# CANnibal.net
KiCad netlist of a schematic drawn in EAGLE
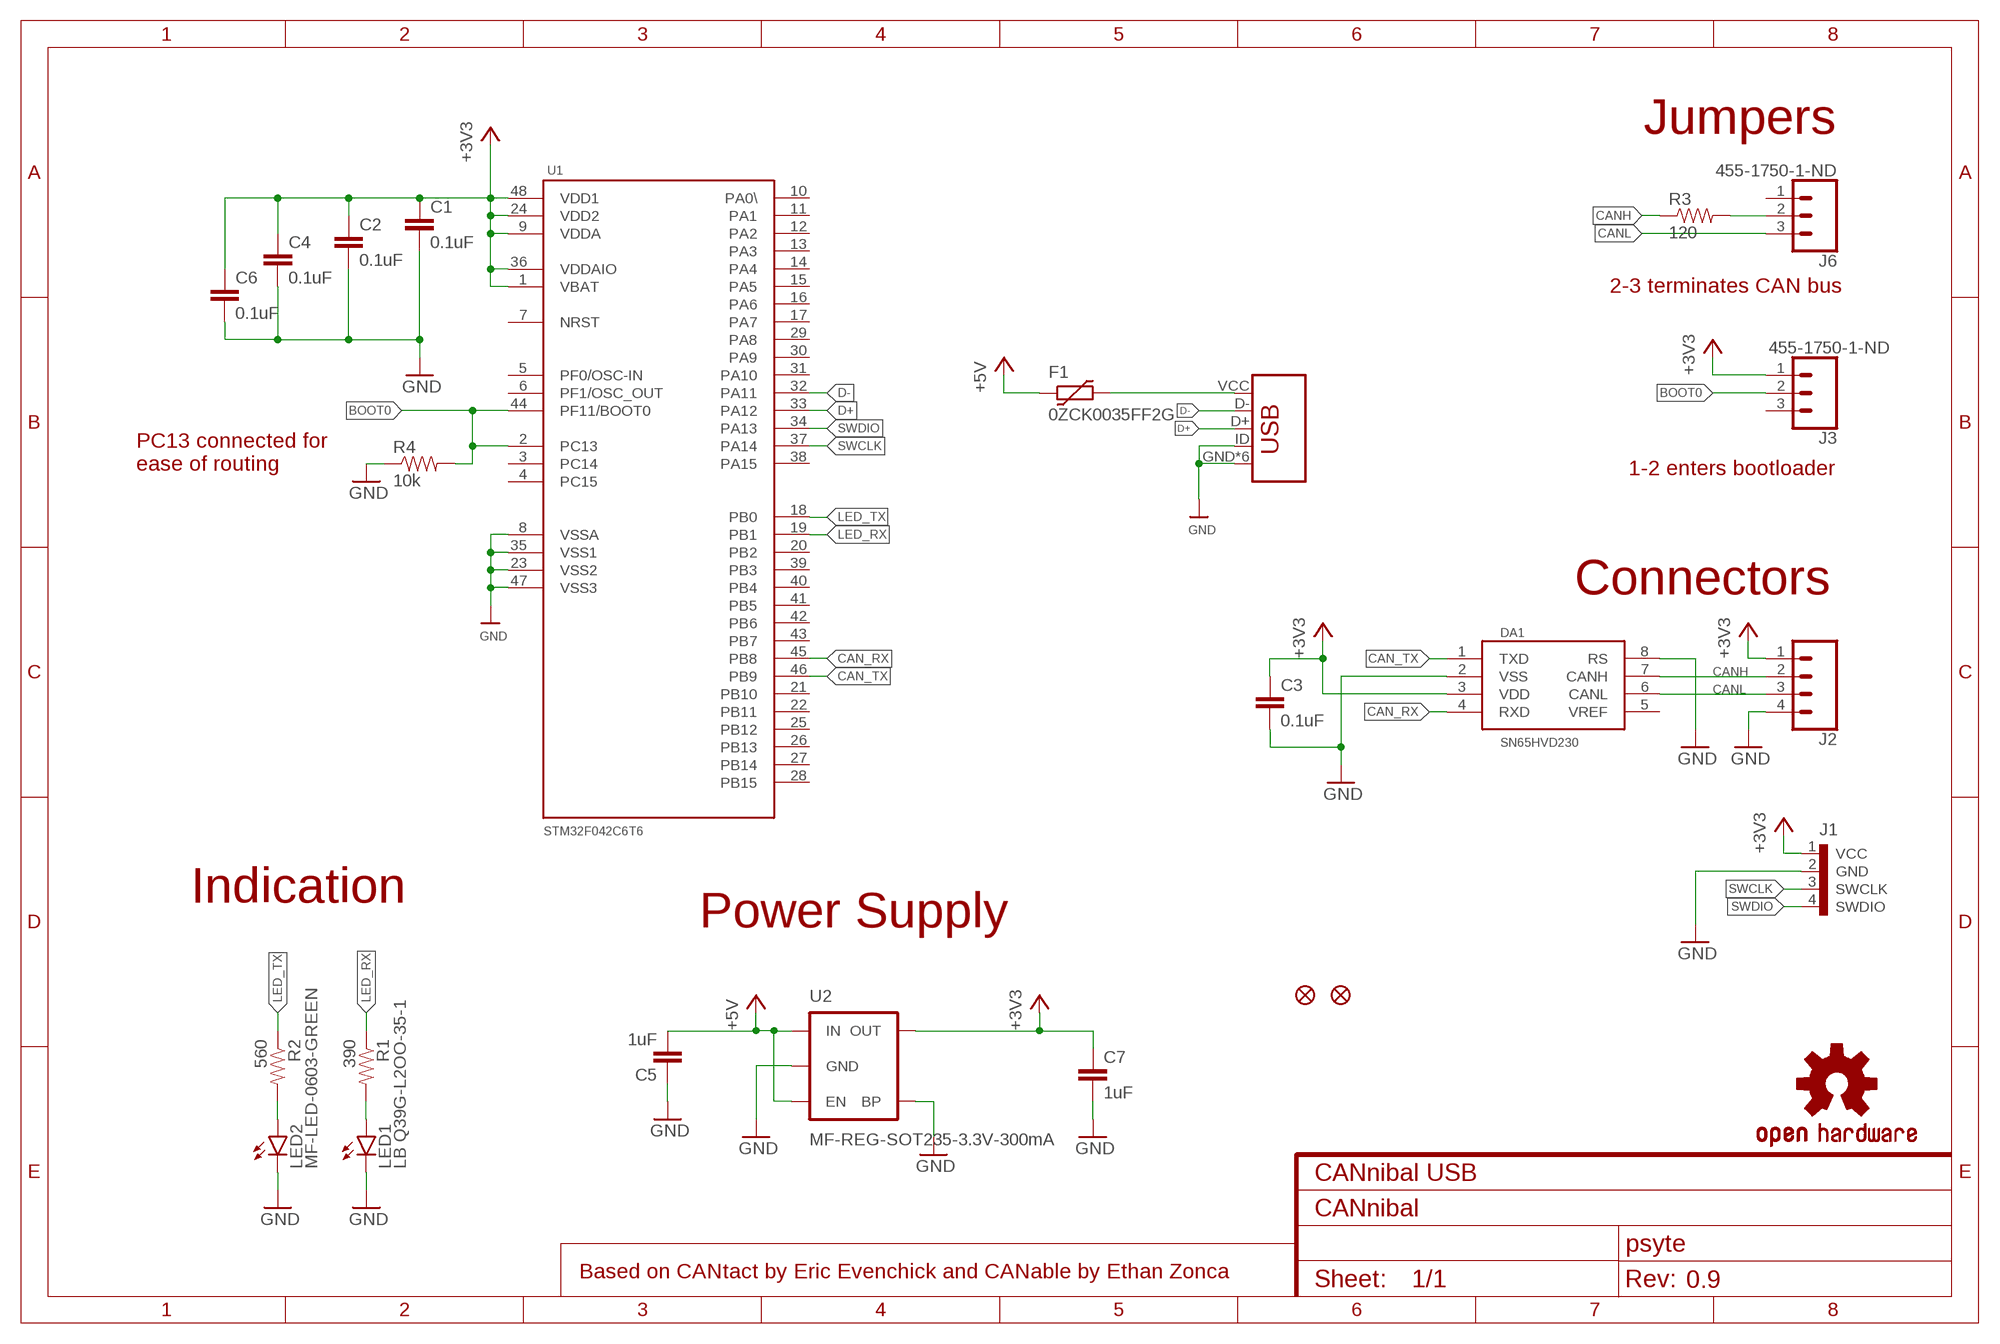
[diagram p0: schematic, sheet 1]

(export (version "E")
  (design (tool "Eeschema 10.0.6"))
  (components
    (comp (ref "C1")
      (value "0.1uF")
      (footprint "eagle-import:0603-CAP")
      (libsource (lib "eagle-import") (part "CAP0603-CAP"))
    )
    (comp (ref "C2")
      (value "0.1uF")
      (footprint "eagle-import:0603-CAP")
      (libsource (lib "eagle-import") (part "CAP0603-CAP"))
    )
    (comp (ref "C3")
      (value "0.1uF")
      (footprint "eagle-import:0603-CAP")
      (libsource (lib "eagle-import") (part "CAP0603-CAP"))
    )
    (comp (ref "C4")
      (value "0.1uF")
      (footprint "eagle-import:0603-CAP")
      (libsource (lib "eagle-import") (part "CAP0603-CAP"))
    )
    (comp (ref "C5")
      (value "1uF")
      (footprint "eagle-import:0603-CAP")
      (libsource (lib "eagle-import") (part "CAP0603-CAP"))
    )
    (comp (ref "C6")
      (value "0.1uF")
      (footprint "eagle-import:0603-CAP")
      (libsource (lib "eagle-import") (part "CAP0603-CAP"))
    )
    (comp (ref "C7")
      (value "1uF")
      (footprint "eagle-import:0603-CAP")
      (libsource (lib "eagle-import") (part "CAP0603-CAP"))
    )
    (comp (ref "DA1")
      (value "SN65HVD230")
      (footprint "eagle-import:SO08")
      (libsource (lib "eagle-import") (part "SN65HVD230"))
    )
    (comp (ref "F1")
      (value "0ZCK0035FF2G")
      (footprint "eagle-import:PTC0805")
      (libsource (lib "eagle-import") (part "FUSE_PTC-0805"))
    )
    (comp (ref "FD1")
      (value "FIDUCIAL1X2")
      (footprint "eagle-import:FIDUCIAL-1X2")
      (libsource (lib "eagle-import") (part "FIDUCIAL1X2"))
    )
    (comp (ref "FD2")
      (value "FIDUCIAL1X2")
      (footprint "eagle-import:FIDUCIAL-1X2")
      (libsource (lib "eagle-import") (part "FIDUCIAL1X2"))
    )
    (comp (ref "J1")
      (value "POGOPIN-CONN-4")
      (footprint "eagle-import:POGOPROG-CONN-4-ALLSMT")
      (libsource (lib "eagle-import") (part "POGOPIN-CONN-4"))
    )
    (comp (ref "J2")
      (value "CONN_04")
      (footprint "eagle-import:1X04")
      (libsource (lib "eagle-import") (part "CONN_04"))
    )
    (comp (ref "J3")
      (value "455-1750-1-ND")
      (footprint "eagle-import:1X03")
      (libsource (lib "eagle-import") (part "CONN_03"))
    )
    (comp (ref "J6")
      (value "455-1750-1-ND")
      (footprint "eagle-import:1X03")
      (libsource (lib "eagle-import") (part "CONN_03"))
    )
    (comp (ref "LED1")
      (value "LB Q39G-L2OO-35-1")
      (footprint "eagle-import:LED-0603")
      (libsource (lib "eagle-import") (part "LED0603"))
    )
    (comp (ref "LED2")
      (value "MF-LED-0603-GREEN")
      (footprint "eagle-import:LED-0603")
      (libsource (lib "eagle-import") (part "LED0603"))
    )
    (comp (ref "LOGO1")
      (value "OSHW-LOGOS")
      (footprint "eagle-import:OSHW-LOGO-S")
      (libsource (lib "eagle-import") (part "OSHW-LOGOS"))
    )
    (comp (ref "R1")
      (value "390")
      (footprint "eagle-import:0603-RES")
      (libsource (lib "eagle-import") (part "RESISTOR0603-RES"))
    )
    (comp (ref "R2")
      (value "560")
      (footprint "eagle-import:0603-RES")
      (libsource (lib "eagle-import") (part "RESISTOR0603-RES"))
    )
    (comp (ref "R3")
      (value "120")
      (footprint "eagle-import:0603-RES")
      (libsource (lib "eagle-import") (part "RESISTOR0603-RES"))
    )
    (comp (ref "R4")
      (value "10k")
      (footprint "eagle-import:0603-RES")
      (libsource (lib "eagle-import") (part "RESISTOR0603-RES"))
    )
    (comp (ref "U$4")
      (value "MICRO-USB-B")
      (footprint "eagle-import:MICRO_USB_4_LEGS")
      (libsource (lib "eagle-import") (part "MICRO-USB-B"))
    )
    (comp (ref "U1")
      (value "STM32F042C6T6")
      (footprint "eagle-import:LQFP48")
      (libsource (lib "eagle-import") (part "STM32F042C6T6"))
    )
    (comp (ref "U2")
      (value "MF-REG-SOT235-3.3V-300mA")
      (footprint "eagle-import:SOT23-5")
      (libsource (lib "eagle-import") (part "MIC52053.3V"))
    )
  )
  (nets
    (net (code "1") (name "+3V3") (class "Default")
      (node (ref "C1") (pin "1") (pinfunction "1_1") (pintype "passive"))
      (node (ref "C2") (pin "1") (pinfunction "1_1") (pintype "passive"))
      (node (ref "C3") (pin "1") (pinfunction "1_1") (pintype "passive"))
      (node (ref "C4") (pin "1") (pinfunction "1_1") (pintype "passive"))
      (node (ref "C6") (pin "1") (pinfunction "1_1") (pintype "passive"))
      (node (ref "C7") (pin "1") (pinfunction "1_1") (pintype "passive"))
      (node (ref "DA1") (pin "3") (pinfunction "VDD_3") (pintype "power_in"))
      (node (ref "J1") (pin "1") (pinfunction "VCC_1") (pintype "bidirectional"))
      (node (ref "J2") (pin "1") (pinfunction "1_1") (pintype "passive"))
      (node (ref "J3") (pin "1") (pinfunction "1_1") (pintype "passive"))
      (node (ref "U1") (pin "1") (pinfunction "VBAT_1") (pintype "bidirectional"))
      (node (ref "U1") (pin "24") (pinfunction "VDD2_24") (pintype "bidirectional"))
      (node (ref "U1") (pin "36") (pinfunction "VDDAIO_36") (pintype "bidirectional"))
      (node (ref "U1") (pin "48") (pinfunction "VDD1_48") (pintype "bidirectional"))
      (node (ref "U1") (pin "9") (pinfunction "VDDA_9") (pintype "bidirectional"))
      (node (ref "U2") (pin "5") (pinfunction "OUT_5") (pintype "passive"))
    )
    (net (code "2") (name "+5V") (class "Default")
      (node (ref "C5") (pin "2") (pinfunction "2_2") (pintype "passive"))
      (node (ref "F1") (pin "1") (pinfunction "1_1") (pintype "passive"))
      (node (ref "U2") (pin "1") (pinfunction "IN_1") (pintype "input"))
      (node (ref "U2") (pin "3") (pinfunction "EN_3") (pintype "input"))
    )
    (net (code "3") (name "BOOT0") (class "Default")
      (node (ref "J3") (pin "2") (pinfunction "2_2") (pintype "passive"))
      (node (ref "R4") (pin "2") (pinfunction "2_2") (pintype "passive"))
      (node (ref "U1") (pin "2") (pinfunction "PC13_2") (pintype "bidirectional"))
      (node (ref "U1") (pin "44") (pinfunction "PF11/BOOT0_44") (pintype "bidirectional"))
    )
    (net (code "4") (name "CANH") (class "Default")
      (node (ref "DA1") (pin "7") (pinfunction "CANH_7") (pintype "bidirectional"))
      (node (ref "J2") (pin "2") (pinfunction "2_2") (pintype "passive"))
      (node (ref "R3") (pin "1") (pinfunction "1_1") (pintype "passive"))
    )
    (net (code "5") (name "CANL") (class "Default")
      (node (ref "DA1") (pin "6") (pinfunction "CANL_6") (pintype "bidirectional"))
      (node (ref "J2") (pin "3") (pinfunction "3_3") (pintype "passive"))
      (node (ref "J6") (pin "3") (pinfunction "3_3") (pintype "passive"))
    )
    (net (code "6") (name "CAN_RX") (class "Default")
      (node (ref "DA1") (pin "4") (pinfunction "RXD_4") (pintype "output"))
      (node (ref "U1") (pin "45") (pinfunction "PB8_45") (pintype "bidirectional"))
    )
    (net (code "7") (name "CAN_TX") (class "Default")
      (node (ref "DA1") (pin "1") (pinfunction "TXD_1") (pintype "input"))
      (node (ref "U1") (pin "46") (pinfunction "PB9_46") (pintype "bidirectional"))
    )
    (net (code "8") (name "D+") (class "Default")
      (node (ref "U$4") (pin "D+") (pinfunction "D+_D+") (pintype "bidirectional"))
      (node (ref "U1") (pin "33") (pinfunction "PA12_33") (pintype "bidirectional"))
    )
    (net (code "9") (name "D-") (class "Default")
      (node (ref "U$4") (pin "D-") (pinfunction "D-_D-") (pintype "bidirectional"))
      (node (ref "U1") (pin "32") (pinfunction "PA11_32") (pintype "bidirectional"))
    )
    (net (code "10") (name "GND") (class "Default")
      (node (ref "C1") (pin "2") (pinfunction "2_2") (pintype "passive"))
      (node (ref "C2") (pin "2") (pinfunction "2_2") (pintype "passive"))
      (node (ref "C3") (pin "2") (pinfunction "2_2") (pintype "passive"))
      (node (ref "C4") (pin "2") (pinfunction "2_2") (pintype "passive"))
      (node (ref "C5") (pin "1") (pinfunction "1_1") (pintype "passive"))
      (node (ref "C6") (pin "2") (pinfunction "2_2") (pintype "passive"))
      (node (ref "C7") (pin "2") (pinfunction "2_2") (pintype "passive"))
      (node (ref "DA1") (pin "2") (pinfunction "VSS_2") (pintype "power_in"))
      (node (ref "DA1") (pin "8") (pinfunction "RS_8") (pintype "input"))
      (node (ref "J1") (pin "2") (pinfunction "GND_2") (pintype "bidirectional"))
      (node (ref "J2") (pin "4") (pinfunction "4_4") (pintype "passive"))
      (node (ref "LED1") (pin "C") (pinfunction "C_C") (pintype "passive"))
      (node (ref "LED2") (pin "C") (pinfunction "C_C") (pintype "passive"))
      (node (ref "R4") (pin "1") (pinfunction "1_1") (pintype "passive"))
      (node (ref "U$4") (pin "GND") (pinfunction "GND_GND") (pintype "bidirectional"))
      (node (ref "U$4") (pin "ID") (pinfunction "ID_ID") (pintype "bidirectional"))
      (node (ref "U$4") (pin "P$1") (pinfunction "GND_P$1") (pintype "bidirectional"))
      (node (ref "U$4") (pin "P$2") (pinfunction "GND_P$2") (pintype "bidirectional"))
      (node (ref "U$4") (pin "P$3") (pinfunction "GND_P$3") (pintype "bidirectional"))
      (node (ref "U$4") (pin "P$4") (pinfunction "GND_P$4") (pintype "bidirectional"))
      (node (ref "U$4") (pin "P$5") (pinfunction "GND_P$5") (pintype "bidirectional"))
      (node (ref "U1") (pin "23") (pinfunction "VSS2_23") (pintype "bidirectional"))
      (node (ref "U1") (pin "35") (pinfunction "VSS1_35") (pintype "bidirectional"))
      (node (ref "U1") (pin "47") (pinfunction "VSS3_47") (pintype "bidirectional"))
      (node (ref "U1") (pin "8") (pinfunction "VSSA_8") (pintype "bidirectional"))
      (node (ref "U2") (pin "2") (pinfunction "GND_2") (pintype "input"))
      (node (ref "U2") (pin "4") (pinfunction "BP_4") (pintype "input"))
    )
    (net (code "11") (name "LED_RX") (class "Default")
      (node (ref "R1") (pin "1") (pinfunction "1_1") (pintype "passive"))
      (node (ref "U1") (pin "19") (pinfunction "PB1_19") (pintype "bidirectional"))
    )
    (net (code "12") (name "LED_TX") (class "Default")
      (node (ref "R2") (pin "1") (pinfunction "1_1") (pintype "passive"))
      (node (ref "U1") (pin "18") (pinfunction "PB0_18") (pintype "bidirectional"))
    )
    (net (code "13") (name "Net-(J6-Pad2)") (class "Default")
      (node (ref "J6") (pin "2") (pinfunction "2_2") (pintype "passive"))
      (node (ref "R3") (pin "2") (pinfunction "2_2") (pintype "passive"))
    )
    (net (code "14") (name "Net-(LED1-PadA)") (class "Default")
      (node (ref "LED1") (pin "A") (pinfunction "A_A") (pintype "passive"))
      (node (ref "R1") (pin "2") (pinfunction "2_2") (pintype "passive"))
    )
    (net (code "15") (name "Net-(LED2-PadA)") (class "Default")
      (node (ref "LED2") (pin "A") (pinfunction "A_A") (pintype "passive"))
      (node (ref "R2") (pin "2") (pinfunction "2_2") (pintype "passive"))
    )
    (net (code "16") (name "Net-(U$4-VBUS)") (class "Default")
      (node (ref "F1") (pin "2") (pinfunction "2_2") (pintype "passive"))
      (node (ref "U$4") (pin "VCC") (pinfunction "VBUS_VCC") (pintype "bidirectional"))
    )
    (net (code "17") (name "SWCLK") (class "Default")
      (node (ref "J1") (pin "3") (pinfunction "SWCLK_3") (pintype "bidirectional"))
      (node (ref "U1") (pin "37") (pinfunction "PA14_37") (pintype "bidirectional"))
    )
    (net (code "18") (name "SWDIO") (class "Default")
      (node (ref "J1") (pin "4") (pinfunction "SWDIO_4") (pintype "bidirectional"))
      (node (ref "U1") (pin "34") (pinfunction "PA13_34") (pintype "bidirectional"))
    )
    (net (code "19") (name "unconnected-(DA1-VREF-Pad5)") (class "Default")
      (node (ref "DA1") (pin "5") (pinfunction "VREF_5") (pintype "passive"))
    )
    (net (code "20") (name "unconnected-(J3-Pad3)") (class "Default")
      (node (ref "J3") (pin "3") (pinfunction "3_3") (pintype "passive"))
    )
    (net (code "21") (name "unconnected-(J6-Pad1)") (class "Default")
      (node (ref "J6") (pin "1") (pinfunction "1_1") (pintype "passive"))
    )
    (net (code "22") (name "unconnected-(U1-NRST-Pad7)") (class "Default")
      (node (ref "U1") (pin "7") (pinfunction "NRST_7") (pintype "bidirectional"))
    )
    (net (code "23") (name "unconnected-(U1-PA0\\-Pad10)") (class "Default")
      (node (ref "U1") (pin "10") (pinfunction "PA0\\_10") (pintype "bidirectional"))
    )
    (net (code "24") (name "unconnected-(U1-PA1-Pad11)") (class "Default")
      (node (ref "U1") (pin "11") (pinfunction "PA1_11") (pintype "bidirectional"))
    )
    (net (code "25") (name "unconnected-(U1-PA2-Pad12)") (class "Default")
      (node (ref "U1") (pin "12") (pinfunction "PA2_12") (pintype "bidirectional"))
    )
    (net (code "26") (name "unconnected-(U1-PA3-Pad13)") (class "Default")
      (node (ref "U1") (pin "13") (pinfunction "PA3_13") (pintype "bidirectional"))
    )
    (net (code "27") (name "unconnected-(U1-PA4-Pad14)") (class "Default")
      (node (ref "U1") (pin "14") (pinfunction "PA4_14") (pintype "bidirectional"))
    )
    (net (code "28") (name "unconnected-(U1-PA5-Pad15)") (class "Default")
      (node (ref "U1") (pin "15") (pinfunction "PA5_15") (pintype "bidirectional"))
    )
    (net (code "29") (name "unconnected-(U1-PA6-Pad16)") (class "Default")
      (node (ref "U1") (pin "16") (pinfunction "PA6_16") (pintype "bidirectional"))
    )
    (net (code "30") (name "unconnected-(U1-PA7-Pad17)") (class "Default")
      (node (ref "U1") (pin "17") (pinfunction "PA7_17") (pintype "bidirectional"))
    )
    (net (code "31") (name "unconnected-(U1-PA8-Pad29)") (class "Default")
      (node (ref "U1") (pin "29") (pinfunction "PA8_29") (pintype "bidirectional"))
    )
    (net (code "32") (name "unconnected-(U1-PA9-Pad30)") (class "Default")
      (node (ref "U1") (pin "30") (pinfunction "PA9_30") (pintype "bidirectional"))
    )
    (net (code "33") (name "unconnected-(U1-PA10-Pad31)") (class "Default")
      (node (ref "U1") (pin "31") (pinfunction "PA10_31") (pintype "bidirectional"))
    )
    (net (code "34") (name "unconnected-(U1-PA15-Pad38)") (class "Default")
      (node (ref "U1") (pin "38") (pinfunction "PA15_38") (pintype "bidirectional"))
    )
    (net (code "35") (name "unconnected-(U1-PB2-Pad20)") (class "Default")
      (node (ref "U1") (pin "20") (pinfunction "PB2_20") (pintype "bidirectional"))
    )
    (net (code "36") (name "unconnected-(U1-PB3-Pad39)") (class "Default")
      (node (ref "U1") (pin "39") (pinfunction "PB3_39") (pintype "bidirectional"))
    )
    (net (code "37") (name "unconnected-(U1-PB4-Pad40)") (class "Default")
      (node (ref "U1") (pin "40") (pinfunction "PB4_40") (pintype "bidirectional"))
    )
    (net (code "38") (name "unconnected-(U1-PB5-Pad41)") (class "Default")
      (node (ref "U1") (pin "41") (pinfunction "PB5_41") (pintype "bidirectional"))
    )
    (net (code "39") (name "unconnected-(U1-PB6-Pad42)") (class "Default")
      (node (ref "U1") (pin "42") (pinfunction "PB6_42") (pintype "bidirectional"))
    )
    (net (code "40") (name "unconnected-(U1-PB7-Pad43)") (class "Default")
      (node (ref "U1") (pin "43") (pinfunction "PB7_43") (pintype "bidirectional"))
    )
    (net (code "41") (name "unconnected-(U1-PB10-Pad21)") (class "Default")
      (node (ref "U1") (pin "21") (pinfunction "PB10_21") (pintype "bidirectional"))
    )
    (net (code "42") (name "unconnected-(U1-PB11-Pad22)") (class "Default")
      (node (ref "U1") (pin "22") (pinfunction "PB11_22") (pintype "bidirectional"))
    )
    (net (code "43") (name "unconnected-(U1-PB12-Pad25)") (class "Default")
      (node (ref "U1") (pin "25") (pinfunction "PB12_25") (pintype "bidirectional"))
    )
    (net (code "44") (name "unconnected-(U1-PB13-Pad26)") (class "Default")
      (node (ref "U1") (pin "26") (pinfunction "PB13_26") (pintype "bidirectional"))
    )
    (net (code "45") (name "unconnected-(U1-PB14-Pad27)") (class "Default")
      (node (ref "U1") (pin "27") (pinfunction "PB14_27") (pintype "bidirectional"))
    )
    (net (code "46") (name "unconnected-(U1-PB15-Pad28)") (class "Default")
      (node (ref "U1") (pin "28") (pinfunction "PB15_28") (pintype "bidirectional"))
    )
    (net (code "47") (name "unconnected-(U1-PC14-Pad3)") (class "Default")
      (node (ref "U1") (pin "3") (pinfunction "PC14_3") (pintype "bidirectional"))
    )
    (net (code "48") (name "unconnected-(U1-PC15-Pad4)") (class "Default")
      (node (ref "U1") (pin "4") (pinfunction "PC15_4") (pintype "bidirectional"))
    )
    (net (code "49") (name "unconnected-(U1-PF0{slash}OSC-IN-Pad5)") (class "Default")
      (node (ref "U1") (pin "5") (pinfunction "PF0/OSC-IN_5") (pintype "bidirectional"))
    )
    (net (code "50") (name "unconnected-(U1-PF1{slash}OSC_OUT-Pad6)") (class "Default")
      (node (ref "U1") (pin "6") (pinfunction "PF1/OSC_OUT_6") (pintype "bidirectional"))
    )
  )
)
